# HallBoards.net
KiCad netlist of a schematic drawn in EAGLE
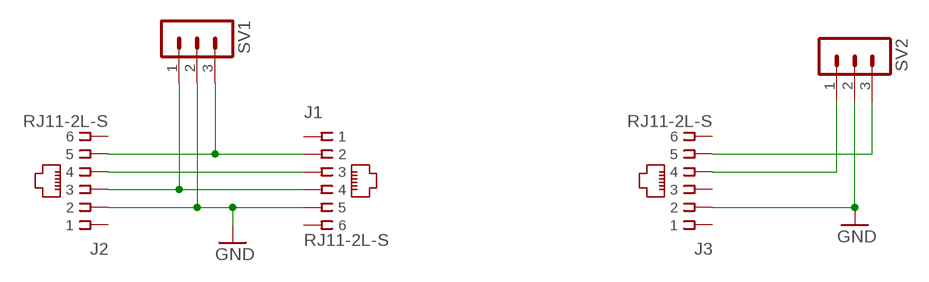
[diagram p0: schematic, sheet 1]

(export (version "E")
  (design (tool "Eeschema 10.0.6"))
  (components
    (comp (ref "J1")
      (value "RJ11-2L-S")
      (footprint "eagle-import:RJ11-NO_SHIELD")
      (libsource (lib "eagle-import") (part "RJ11-2L-S"))
    )
    (comp (ref "J2")
      (value "RJ11-2L-S")
      (footprint "eagle-import:RJ11-NO_SHIELD")
      (libsource (lib "eagle-import") (part "RJ11-2L-S"))
    )
    (comp (ref "J3")
      (value "RJ11-2L-S")
      (footprint "eagle-import:RJ11-NO_SHIELD")
      (libsource (lib "eagle-import") (part "RJ11-2L-S"))
    )
    (comp (ref "SV1")
      (value "MA03-1")
      (footprint "eagle-import:MA03-1")
      (libsource (lib "eagle-import") (part "MA03-1"))
    )
    (comp (ref "SV2")
      (value "MA03-1")
      (footprint "eagle-import:MA03-1")
      (libsource (lib "eagle-import") (part "MA03-1"))
    )
  )
  (nets
    (net (code "1") (name "GND") (class "Default")
      (node (ref "J1") (pin "5") (pinfunction "5_5") (pintype "passive"))
      (node (ref "J2") (pin "2") (pinfunction "2_2") (pintype "passive"))
      (node (ref "J3") (pin "2") (pinfunction "2_2") (pintype "passive"))
      (node (ref "SV1") (pin "2") (pinfunction "2_2") (pintype "passive"))
      (node (ref "SV2") (pin "2") (pinfunction "2_2") (pintype "passive"))
    )
    (net (code "2") (name "Net-(J1-Pad2)") (class "Default")
      (node (ref "J1") (pin "2") (pinfunction "2_2") (pintype "passive"))
      (node (ref "J2") (pin "5") (pinfunction "5_5") (pintype "passive"))
      (node (ref "SV1") (pin "3") (pinfunction "3_3") (pintype "passive"))
    )
    (net (code "3") (name "Net-(J1-Pad3)") (class "Default")
      (node (ref "J1") (pin "3") (pinfunction "3_3") (pintype "passive"))
      (node (ref "J2") (pin "4") (pinfunction "4_4") (pintype "passive"))
    )
    (net (code "4") (name "Net-(J1-Pad4)") (class "Default")
      (node (ref "J1") (pin "4") (pinfunction "4_4") (pintype "passive"))
      (node (ref "J2") (pin "3") (pinfunction "3_3") (pintype "passive"))
      (node (ref "SV1") (pin "1") (pinfunction "1_1") (pintype "passive"))
    )
    (net (code "5") (name "Net-(J3-Pad4)") (class "Default")
      (node (ref "J3") (pin "4") (pinfunction "4_4") (pintype "passive"))
      (node (ref "SV2") (pin "1") (pinfunction "1_1") (pintype "passive"))
    )
    (net (code "6") (name "Net-(J3-Pad5)") (class "Default")
      (node (ref "J3") (pin "5") (pinfunction "5_5") (pintype "passive"))
      (node (ref "SV2") (pin "3") (pinfunction "3_3") (pintype "passive"))
    )
    (net (code "7") (name "unconnected-(J1-Pad1)") (class "Default")
      (node (ref "J1") (pin "1") (pinfunction "1_1") (pintype "passive"))
    )
    (net (code "8") (name "unconnected-(J1-Pad6)") (class "Default")
      (node (ref "J1") (pin "6") (pinfunction "6_6") (pintype "passive"))
    )
    (net (code "9") (name "unconnected-(J2-Pad1)") (class "Default")
      (node (ref "J2") (pin "1") (pinfunction "1_1") (pintype "passive"))
    )
    (net (code "10") (name "unconnected-(J2-Pad6)") (class "Default")
      (node (ref "J2") (pin "6") (pinfunction "6_6") (pintype "passive"))
    )
    (net (code "11") (name "unconnected-(J3-Pad1)") (class "Default")
      (node (ref "J3") (pin "1") (pinfunction "1_1") (pintype "passive"))
    )
    (net (code "12") (name "unconnected-(J3-Pad3)") (class "Default")
      (node (ref "J3") (pin "3") (pinfunction "3_3") (pintype "passive"))
    )
    (net (code "13") (name "unconnected-(J3-Pad6)") (class "Default")
      (node (ref "J3") (pin "6") (pinfunction "6_6") (pintype "passive"))
    )
  )
)
